# SAMD21-breakout_v1.net
KiCad netlist of a schematic drawn in EAGLE
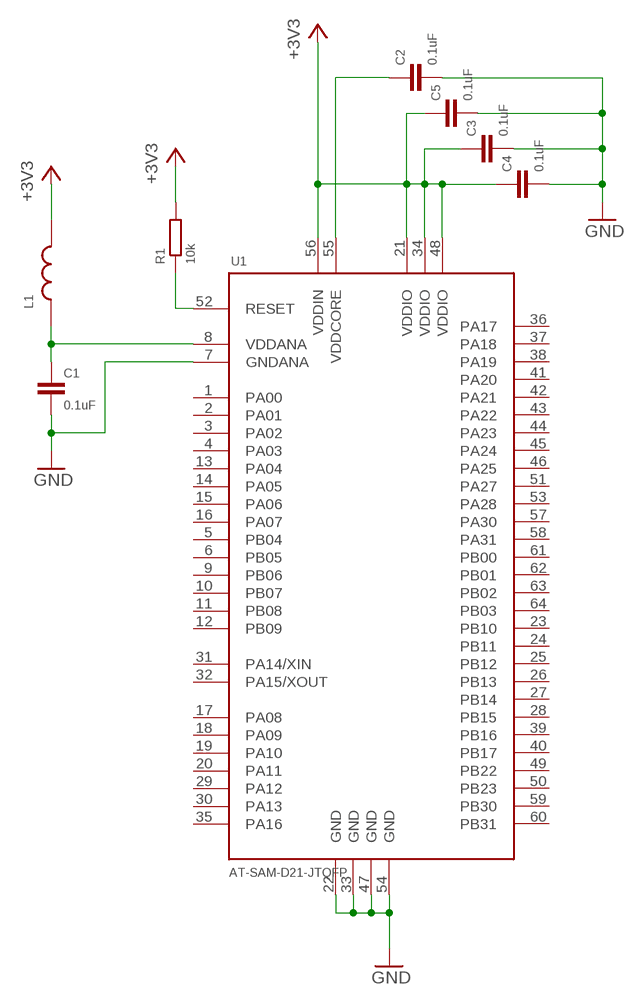
[diagram p0: schematic, sheet 1]

(export (version "E")
  (design (tool "Eeschema 10.0.6"))
  (components
    (comp (ref "C1")
      (value "0.1uF")
      (footprint "eagle-import:CAP-0603")
      (libsource (lib "eagle-import") (part "CAP0603"))
    )
    (comp (ref "C2")
      (value "0.1uF")
      (footprint "eagle-import:CAP-0603")
      (libsource (lib "eagle-import") (part "CAP0603"))
    )
    (comp (ref "C3")
      (value "0.1uF")
      (footprint "eagle-import:CAP-0603")
      (libsource (lib "eagle-import") (part "CAP0603"))
    )
    (comp (ref "C4")
      (value "0.1uF")
      (footprint "eagle-import:CAP-0603")
      (libsource (lib "eagle-import") (part "CAP0603"))
    )
    (comp (ref "C5")
      (value "0.1uF")
      (footprint "eagle-import:CAP-0603")
      (libsource (lib "eagle-import") (part "CAP0603"))
    )
    (comp (ref "L1")
      (value "INDUCTOR0603")
      (footprint "eagle-import:IND-0603")
      (libsource (lib "eagle-import") (part "INDUCTOR0603"))
    )
    (comp (ref "R1")
      (value "10k")
      (footprint "eagle-import:RES-0603")
      (libsource (lib "eagle-import") (part "RESISTOR0603"))
    )
    (comp (ref "U1")
      (value "AT-SAM-D21-JTQFP")
      (footprint "eagle-import:TQFP-64")
      (libsource (lib "eagle-import") (part "AT-SAM-D21-JTQFP"))
    )
  )
  (nets
    (net (code "1") (name "+3V3") (class "Default")
      (node (ref "C3") (pin "1") (pinfunction "1_1") (pintype "passive"))
      (node (ref "C4") (pin "1") (pinfunction "1_1") (pintype "passive"))
      (node (ref "C5") (pin "1") (pinfunction "1_1") (pintype "passive"))
      (node (ref "L1") (pin "2") (pinfunction "2_2") (pintype "passive"))
      (node (ref "R1") (pin "2") (pinfunction "2_2") (pintype "passive"))
      (node (ref "U1") (pin "21") (pinfunction "VDDIO_21") (pintype "power_in"))
      (node (ref "U1") (pin "34") (pinfunction "VDDIO_34") (pintype "power_in"))
      (node (ref "U1") (pin "48") (pinfunction "VDDIO_48") (pintype "power_in"))
      (node (ref "U1") (pin "56") (pinfunction "VDDIN_56") (pintype "power_in"))
    )
    (net (code "2") (name "GND") (class "Default")
      (node (ref "C1") (pin "2") (pinfunction "2_2") (pintype "passive"))
      (node (ref "C2") (pin "2") (pinfunction "2_2") (pintype "passive"))
      (node (ref "C3") (pin "2") (pinfunction "2_2") (pintype "passive"))
      (node (ref "C4") (pin "2") (pinfunction "2_2") (pintype "passive"))
      (node (ref "C5") (pin "2") (pinfunction "2_2") (pintype "passive"))
      (node (ref "U1") (pin "22") (pinfunction "GND_22") (pintype "power_in"))
      (node (ref "U1") (pin "33") (pinfunction "GND_33") (pintype "power_in"))
      (node (ref "U1") (pin "47") (pinfunction "GND_47") (pintype "power_in"))
      (node (ref "U1") (pin "54") (pinfunction "GND_54") (pintype "power_in"))
      (node (ref "U1") (pin "7") (pinfunction "GNDANA_7") (pintype "power_in"))
    )
    (net (code "3") (name "Net-(U1-RESET)") (class "Default")
      (node (ref "R1") (pin "1") (pinfunction "1_1") (pintype "passive"))
      (node (ref "U1") (pin "52") (pinfunction "RESET_52") (pintype "bidirectional"))
    )
    (net (code "4") (name "Net-(U1-VDDANA)") (class "Default")
      (node (ref "C1") (pin "1") (pinfunction "1_1") (pintype "passive"))
      (node (ref "L1") (pin "1") (pinfunction "1_1") (pintype "passive"))
      (node (ref "U1") (pin "8") (pinfunction "VDDANA_8") (pintype "power_in"))
    )
    (net (code "5") (name "Net-(U1-VDDCORE)") (class "Default")
      (node (ref "C2") (pin "1") (pinfunction "1_1") (pintype "passive"))
      (node (ref "U1") (pin "55") (pinfunction "VDDCORE_55") (pintype "output"))
    )
    (net (code "6") (name "unconnected-(U1-PA00-Pad1)") (class "Default")
      (node (ref "U1") (pin "1") (pinfunction "PA00_1") (pintype "bidirectional"))
    )
    (net (code "7") (name "unconnected-(U1-PA01-Pad2)") (class "Default")
      (node (ref "U1") (pin "2") (pinfunction "PA01_2") (pintype "bidirectional"))
    )
    (net (code "8") (name "unconnected-(U1-PA02-Pad3)") (class "Default")
      (node (ref "U1") (pin "3") (pinfunction "PA02_3") (pintype "bidirectional"))
    )
    (net (code "9") (name "unconnected-(U1-PA03-Pad4)") (class "Default")
      (node (ref "U1") (pin "4") (pinfunction "PA03_4") (pintype "bidirectional"))
    )
    (net (code "10") (name "unconnected-(U1-PA04-Pad13)") (class "Default")
      (node (ref "U1") (pin "13") (pinfunction "PA04_13") (pintype "bidirectional"))
    )
    (net (code "11") (name "unconnected-(U1-PA05-Pad14)") (class "Default")
      (node (ref "U1") (pin "14") (pinfunction "PA05_14") (pintype "bidirectional"))
    )
    (net (code "12") (name "unconnected-(U1-PA06-Pad15)") (class "Default")
      (node (ref "U1") (pin "15") (pinfunction "PA06_15") (pintype "bidirectional"))
    )
    (net (code "13") (name "unconnected-(U1-PA07-Pad16)") (class "Default")
      (node (ref "U1") (pin "16") (pinfunction "PA07_16") (pintype "bidirectional"))
    )
    (net (code "14") (name "unconnected-(U1-PA08-Pad17)") (class "Default")
      (node (ref "U1") (pin "17") (pinfunction "PA08_17") (pintype "bidirectional"))
    )
    (net (code "15") (name "unconnected-(U1-PA09-Pad18)") (class "Default")
      (node (ref "U1") (pin "18") (pinfunction "PA09_18") (pintype "bidirectional"))
    )
    (net (code "16") (name "unconnected-(U1-PA10-Pad19)") (class "Default")
      (node (ref "U1") (pin "19") (pinfunction "PA10_19") (pintype "bidirectional"))
    )
    (net (code "17") (name "unconnected-(U1-PA11-Pad20)") (class "Default")
      (node (ref "U1") (pin "20") (pinfunction "PA11_20") (pintype "bidirectional"))
    )
    (net (code "18") (name "unconnected-(U1-PA12-Pad29)") (class "Default")
      (node (ref "U1") (pin "29") (pinfunction "PA12_29") (pintype "bidirectional"))
    )
    (net (code "19") (name "unconnected-(U1-PA13-Pad30)") (class "Default")
      (node (ref "U1") (pin "30") (pinfunction "PA13_30") (pintype "bidirectional"))
    )
    (net (code "20") (name "unconnected-(U1-PA14{slash}XIN-Pad31)") (class "Default")
      (node (ref "U1") (pin "31") (pinfunction "PA14/XIN_31") (pintype "bidirectional"))
    )
    (net (code "21") (name "unconnected-(U1-PA15{slash}XOUT-Pad32)") (class "Default")
      (node (ref "U1") (pin "32") (pinfunction "PA15/XOUT_32") (pintype "bidirectional"))
    )
    (net (code "22") (name "unconnected-(U1-PA16-Pad35)") (class "Default")
      (node (ref "U1") (pin "35") (pinfunction "PA16_35") (pintype "bidirectional"))
    )
    (net (code "23") (name "unconnected-(U1-PA17-Pad36)") (class "Default")
      (node (ref "U1") (pin "36") (pinfunction "PA17_36") (pintype "bidirectional"))
    )
    (net (code "24") (name "unconnected-(U1-PA18-Pad37)") (class "Default")
      (node (ref "U1") (pin "37") (pinfunction "PA18_37") (pintype "bidirectional"))
    )
    (net (code "25") (name "unconnected-(U1-PA19-Pad38)") (class "Default")
      (node (ref "U1") (pin "38") (pinfunction "PA19_38") (pintype "bidirectional"))
    )
    (net (code "26") (name "unconnected-(U1-PA20-Pad41)") (class "Default")
      (node (ref "U1") (pin "41") (pinfunction "PA20_41") (pintype "bidirectional"))
    )
    (net (code "27") (name "unconnected-(U1-PA21-Pad42)") (class "Default")
      (node (ref "U1") (pin "42") (pinfunction "PA21_42") (pintype "bidirectional"))
    )
    (net (code "28") (name "unconnected-(U1-PA22-Pad43)") (class "Default")
      (node (ref "U1") (pin "43") (pinfunction "PA22_43") (pintype "bidirectional"))
    )
    (net (code "29") (name "unconnected-(U1-PA23-Pad44)") (class "Default")
      (node (ref "U1") (pin "44") (pinfunction "PA23_44") (pintype "bidirectional"))
    )
    (net (code "30") (name "unconnected-(U1-PA24-Pad45)") (class "Default")
      (node (ref "U1") (pin "45") (pinfunction "PA24_45") (pintype "bidirectional"))
    )
    (net (code "31") (name "unconnected-(U1-PA25-Pad46)") (class "Default")
      (node (ref "U1") (pin "46") (pinfunction "PA25_46") (pintype "bidirectional"))
    )
    (net (code "32") (name "unconnected-(U1-PA27-Pad51)") (class "Default")
      (node (ref "U1") (pin "51") (pinfunction "PA27_51") (pintype "bidirectional"))
    )
    (net (code "33") (name "unconnected-(U1-PA28-Pad53)") (class "Default")
      (node (ref "U1") (pin "53") (pinfunction "PA28_53") (pintype "bidirectional"))
    )
    (net (code "34") (name "unconnected-(U1-PA30-Pad57)") (class "Default")
      (node (ref "U1") (pin "57") (pinfunction "PA30_57") (pintype "bidirectional"))
    )
    (net (code "35") (name "unconnected-(U1-PA31-Pad58)") (class "Default")
      (node (ref "U1") (pin "58") (pinfunction "PA31_58") (pintype "bidirectional"))
    )
    (net (code "36") (name "unconnected-(U1-PB00-Pad61)") (class "Default")
      (node (ref "U1") (pin "61") (pinfunction "PB00_61") (pintype "bidirectional"))
    )
    (net (code "37") (name "unconnected-(U1-PB01-Pad62)") (class "Default")
      (node (ref "U1") (pin "62") (pinfunction "PB01_62") (pintype "bidirectional"))
    )
    (net (code "38") (name "unconnected-(U1-PB02-Pad63)") (class "Default")
      (node (ref "U1") (pin "63") (pinfunction "PB02_63") (pintype "bidirectional"))
    )
    (net (code "39") (name "unconnected-(U1-PB03-Pad64)") (class "Default")
      (node (ref "U1") (pin "64") (pinfunction "PB03_64") (pintype "bidirectional"))
    )
    (net (code "40") (name "unconnected-(U1-PB04-Pad5)") (class "Default")
      (node (ref "U1") (pin "5") (pinfunction "PB04_5") (pintype "bidirectional"))
    )
    (net (code "41") (name "unconnected-(U1-PB05-Pad6)") (class "Default")
      (node (ref "U1") (pin "6") (pinfunction "PB05_6") (pintype "bidirectional"))
    )
    (net (code "42") (name "unconnected-(U1-PB06-Pad9)") (class "Default")
      (node (ref "U1") (pin "9") (pinfunction "PB06_9") (pintype "bidirectional"))
    )
    (net (code "43") (name "unconnected-(U1-PB07-Pad10)") (class "Default")
      (node (ref "U1") (pin "10") (pinfunction "PB07_10") (pintype "bidirectional"))
    )
    (net (code "44") (name "unconnected-(U1-PB08-Pad11)") (class "Default")
      (node (ref "U1") (pin "11") (pinfunction "PB08_11") (pintype "bidirectional"))
    )
    (net (code "45") (name "unconnected-(U1-PB09-Pad12)") (class "Default")
      (node (ref "U1") (pin "12") (pinfunction "PB09_12") (pintype "bidirectional"))
    )
    (net (code "46") (name "unconnected-(U1-PB10-Pad23)") (class "Default")
      (node (ref "U1") (pin "23") (pinfunction "PB10_23") (pintype "bidirectional"))
    )
    (net (code "47") (name "unconnected-(U1-PB11-Pad24)") (class "Default")
      (node (ref "U1") (pin "24") (pinfunction "PB11_24") (pintype "bidirectional"))
    )
    (net (code "48") (name "unconnected-(U1-PB12-Pad25)") (class "Default")
      (node (ref "U1") (pin "25") (pinfunction "PB12_25") (pintype "bidirectional"))
    )
    (net (code "49") (name "unconnected-(U1-PB13-Pad26)") (class "Default")
      (node (ref "U1") (pin "26") (pinfunction "PB13_26") (pintype "bidirectional"))
    )
    (net (code "50") (name "unconnected-(U1-PB14-Pad27)") (class "Default")
      (node (ref "U1") (pin "27") (pinfunction "PB14_27") (pintype "bidirectional"))
    )
    (net (code "51") (name "unconnected-(U1-PB15-Pad28)") (class "Default")
      (node (ref "U1") (pin "28") (pinfunction "PB15_28") (pintype "bidirectional"))
    )
    (net (code "52") (name "unconnected-(U1-PB16-Pad39)") (class "Default")
      (node (ref "U1") (pin "39") (pinfunction "PB16_39") (pintype "bidirectional"))
    )
    (net (code "53") (name "unconnected-(U1-PB17-Pad40)") (class "Default")
      (node (ref "U1") (pin "40") (pinfunction "PB17_40") (pintype "bidirectional"))
    )
    (net (code "54") (name "unconnected-(U1-PB22-Pad49)") (class "Default")
      (node (ref "U1") (pin "49") (pinfunction "PB22_49") (pintype "bidirectional"))
    )
    (net (code "55") (name "unconnected-(U1-PB23-Pad50)") (class "Default")
      (node (ref "U1") (pin "50") (pinfunction "PB23_50") (pintype "bidirectional"))
    )
    (net (code "56") (name "unconnected-(U1-PB30-Pad59)") (class "Default")
      (node (ref "U1") (pin "59") (pinfunction "PB30_59") (pintype "bidirectional"))
    )
    (net (code "57") (name "unconnected-(U1-PB31-Pad60)") (class "Default")
      (node (ref "U1") (pin "60") (pinfunction "PB31_60") (pintype "bidirectional"))
    )
  )
)
